# x-BIMU_Bluetooth.net
KiCad netlist of a schematic drawn in EAGLE
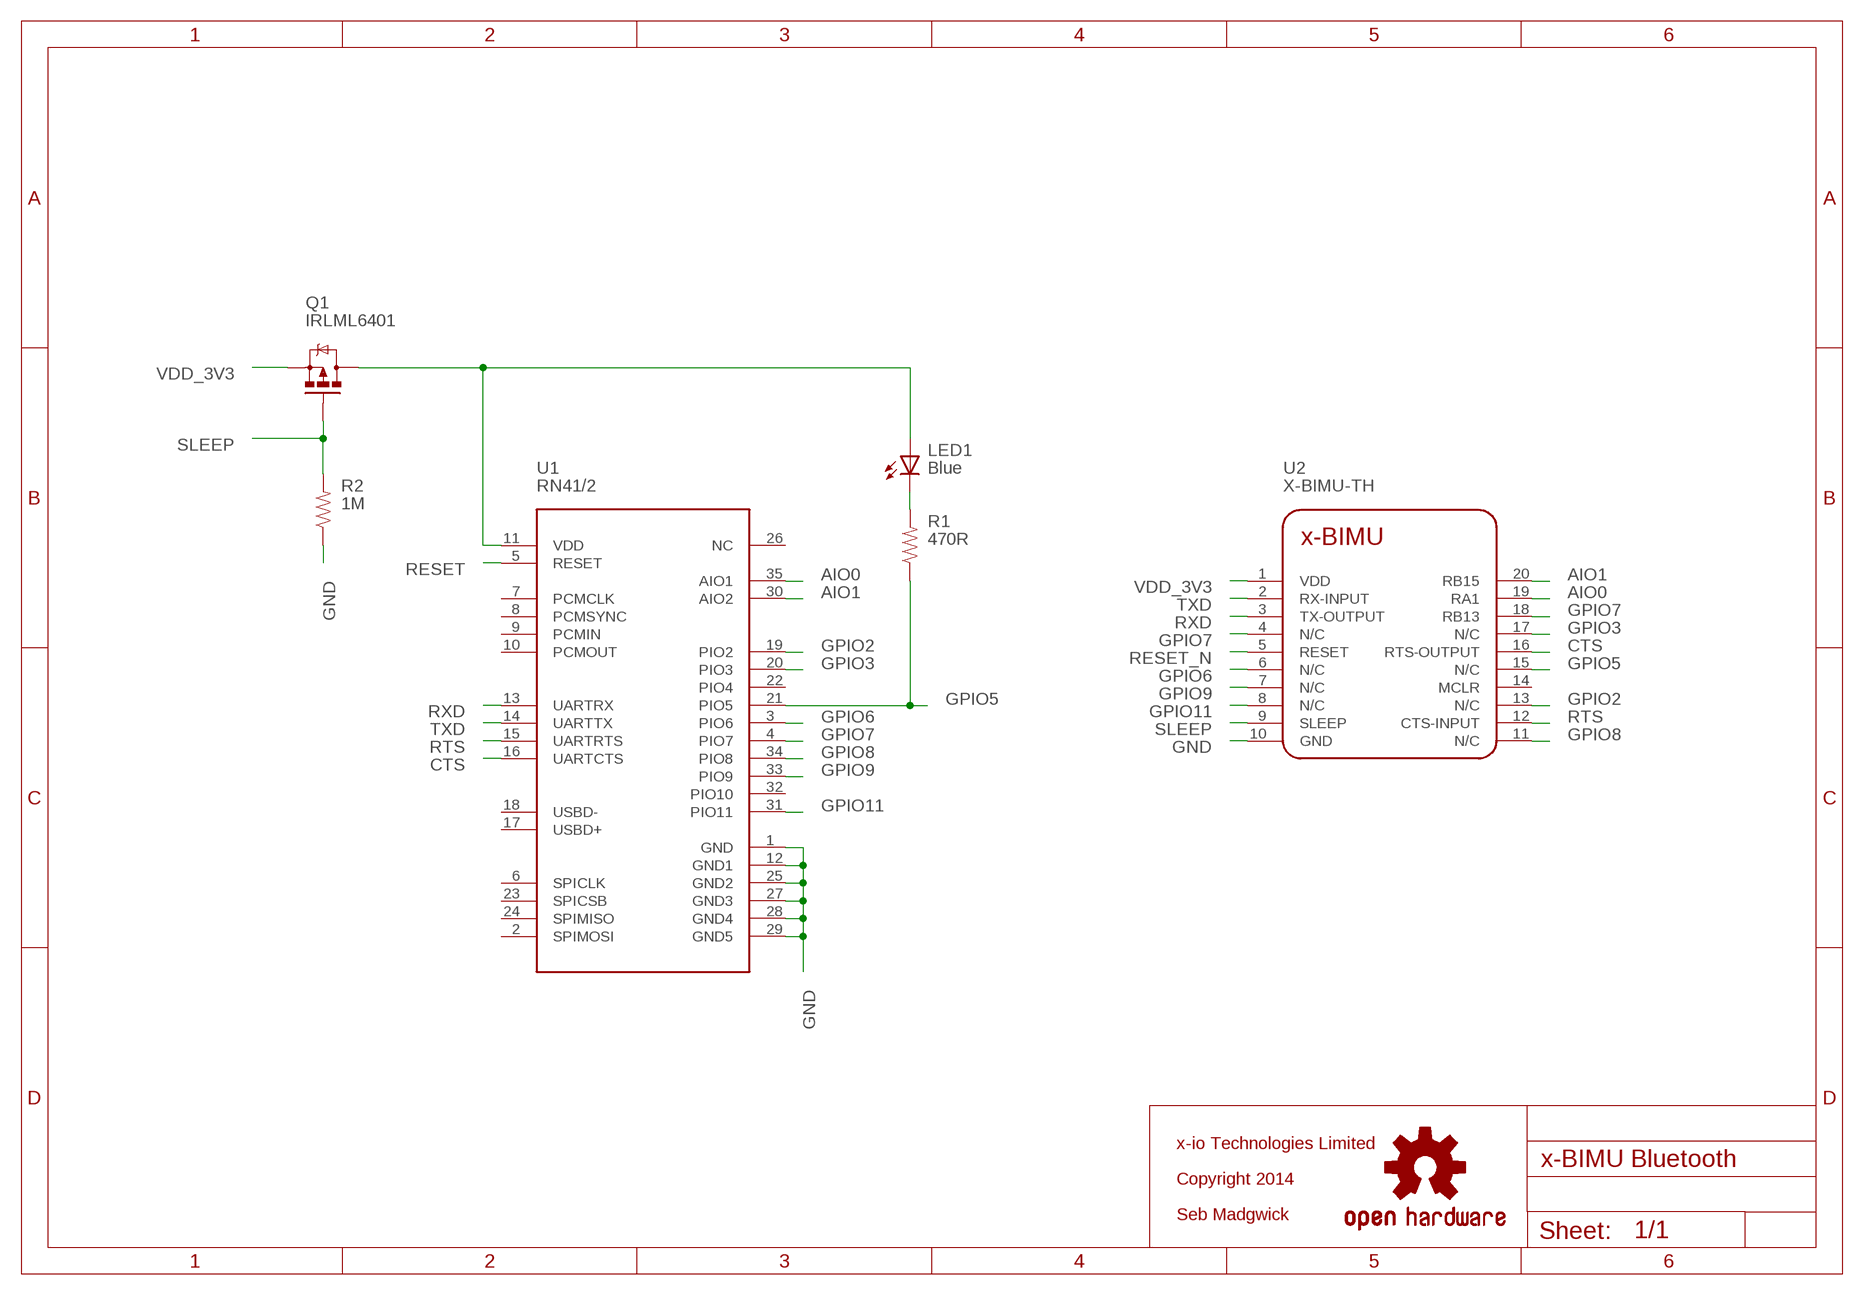
[diagram p0: schematic, sheet 1]

(export (version "E")
  (design (tool "Eeschema 10.0.6"))
  (components
    (comp (ref "LED1")
      (value "Blue")
      (footprint "eagle-import:LED-0603")
      (libsource (lib "eagle-import") (part "LED0603"))
    )
    (comp (ref "Q1")
      (value "IRLML6401")
      (footprint "eagle-import:SOT23")
      (libsource (lib "eagle-import") (part "MOSFET-PCHANNEL"))
    )
    (comp (ref "R1")
      (value "470R")
      (footprint "eagle-import:0402-RES")
      (libsource (lib "eagle-import") (part "RESISTOR0402-RES"))
    )
    (comp (ref "R2")
      (value "1M")
      (footprint "eagle-import:0402-RES")
      (libsource (lib "eagle-import") (part "RESISTOR0402-RES"))
    )
    (comp (ref "U$3")
      (value "OSHW-LOGOS")
      (footprint "eagle-import:OSHW-LOGO-S")
      (libsource (lib "eagle-import") (part "OSHW-LOGOS"))
    )
    (comp (ref "U1")
      (value "RN41/2")
      (footprint "eagle-import:RN41")
      (libsource (lib "eagle-import") (part "BLUETOOTH-RN41{dblquote}"))
    )
    (comp (ref "U2")
      (value "X-BIMU-TH")
      (footprint "eagle-import:X-BIMU_TH")
      (libsource (lib "eagle-import") (part "X-BIMU-TH"))
    )
  )
  (nets
    (net (code "1") (name "/AIO0") (class "Default")
      (node (ref "U1") (pin "35") (pinfunction "AIO1_35") (pintype "bidirectional"))
      (node (ref "U2") (pin "19") (pinfunction "RA1_19") (pintype "bidirectional"))
    )
    (net (code "2") (name "/AIO1") (class "Default")
      (node (ref "U1") (pin "30") (pinfunction "AIO2_30") (pintype "bidirectional"))
      (node (ref "U2") (pin "20") (pinfunction "RB15_20") (pintype "bidirectional"))
    )
    (net (code "3") (name "/CTS") (class "Default")
      (node (ref "U1") (pin "16") (pinfunction "UARTCTS_16") (pintype "bidirectional"))
      (node (ref "U2") (pin "16") (pinfunction "RTS-OUTPUT_16") (pintype "bidirectional"))
    )
    (net (code "4") (name "/GND") (class "Default")
      (node (ref "R2") (pin "1") (pinfunction "1_1") (pintype "passive"))
      (node (ref "U1") (pin "1") (pinfunction "GND_1") (pintype "bidirectional"))
      (node (ref "U1") (pin "12") (pinfunction "GND1_12") (pintype "bidirectional"))
      (node (ref "U1") (pin "25") (pinfunction "GND2_25") (pintype "bidirectional"))
      (node (ref "U1") (pin "27") (pinfunction "GND3_27") (pintype "bidirectional"))
      (node (ref "U1") (pin "28") (pinfunction "GND4_28") (pintype "bidirectional"))
      (node (ref "U1") (pin "29") (pinfunction "GND5_29") (pintype "bidirectional"))
      (node (ref "U2") (pin "10") (pinfunction "GND_10") (pintype "bidirectional"))
    )
    (net (code "5") (name "/GPIO2") (class "Default")
      (node (ref "U1") (pin "19") (pinfunction "PIO2_19") (pintype "bidirectional"))
      (node (ref "U2") (pin "13") (pinfunction "N/C_13") (pintype "bidirectional"))
    )
    (net (code "6") (name "/GPIO3") (class "Default")
      (node (ref "U1") (pin "20") (pinfunction "PIO3_20") (pintype "bidirectional"))
      (node (ref "U2") (pin "17") (pinfunction "N/C_17") (pintype "bidirectional"))
    )
    (net (code "7") (name "/GPIO5") (class "Default")
      (node (ref "R1") (pin "1") (pinfunction "1_1") (pintype "passive"))
      (node (ref "U1") (pin "21") (pinfunction "PIO5_21") (pintype "bidirectional"))
      (node (ref "U2") (pin "15") (pinfunction "N/C_15") (pintype "bidirectional"))
    )
    (net (code "8") (name "/GPIO6") (class "Default")
      (node (ref "U1") (pin "3") (pinfunction "PIO6_3") (pintype "bidirectional"))
      (node (ref "U2") (pin "6") (pinfunction "N/C_6") (pintype "bidirectional"))
    )
    (net (code "9") (name "/GPIO7") (class "Default")
      (node (ref "U1") (pin "4") (pinfunction "PIO7_4") (pintype "bidirectional"))
      (node (ref "U2") (pin "18") (pinfunction "RB13_18") (pintype "bidirectional"))
      (node (ref "U2") (pin "4") (pinfunction "N/C_4") (pintype "bidirectional"))
    )
    (net (code "10") (name "/GPIO8") (class "Default")
      (node (ref "U1") (pin "34") (pinfunction "PIO8_34") (pintype "bidirectional"))
      (node (ref "U2") (pin "11") (pinfunction "N/C_11") (pintype "bidirectional"))
    )
    (net (code "11") (name "/GPIO9") (class "Default")
      (node (ref "U1") (pin "33") (pinfunction "PIO9_33") (pintype "bidirectional"))
      (node (ref "U2") (pin "7") (pinfunction "N/C_7") (pintype "bidirectional"))
    )
    (net (code "12") (name "/GPIO11") (class "Default")
      (node (ref "U1") (pin "31") (pinfunction "PIO11_31") (pintype "bidirectional"))
      (node (ref "U2") (pin "8") (pinfunction "N/C_8") (pintype "bidirectional"))
    )
    (net (code "13") (name "/RESET") (class "Default")
      (node (ref "U1") (pin "5") (pinfunction "RESET_5") (pintype "bidirectional"))
    )
    (net (code "14") (name "/RESET_N") (class "Default")
      (node (ref "U2") (pin "5") (pinfunction "RESET_5") (pintype "bidirectional"))
    )
    (net (code "15") (name "/RTS") (class "Default")
      (node (ref "U1") (pin "15") (pinfunction "UARTRTS_15") (pintype "bidirectional"))
      (node (ref "U2") (pin "12") (pinfunction "CTS-INPUT_12") (pintype "bidirectional"))
    )
    (net (code "16") (name "/RXD") (class "Default")
      (node (ref "U1") (pin "13") (pinfunction "UARTRX_13") (pintype "bidirectional"))
      (node (ref "U2") (pin "3") (pinfunction "TX-OUTPUT_3") (pintype "bidirectional"))
    )
    (net (code "17") (name "/SLEEP") (class "Default")
      (node (ref "Q1") (pin "1") (pinfunction "G_1") (pintype "passive"))
      (node (ref "R2") (pin "2") (pinfunction "2_2") (pintype "passive"))
      (node (ref "U2") (pin "9") (pinfunction "SLEEP_9") (pintype "bidirectional"))
    )
    (net (code "18") (name "/TXD") (class "Default")
      (node (ref "U1") (pin "14") (pinfunction "UARTTX_14") (pintype "bidirectional"))
      (node (ref "U2") (pin "2") (pinfunction "RX-INPUT_2") (pintype "bidirectional"))
    )
    (net (code "19") (name "/VDD_3V3") (class "Default")
      (node (ref "Q1") (pin "2") (pinfunction "S_2") (pintype "passive"))
      (node (ref "U2") (pin "1") (pinfunction "VDD_1") (pintype "bidirectional"))
    )
    (net (code "20") (name "Net-(LED1-PadC)") (class "Default")
      (node (ref "LED1") (pin "C") (pinfunction "C_C") (pintype "passive"))
      (node (ref "R1") (pin "2") (pinfunction "2_2") (pintype "passive"))
    )
    (net (code "21") (name "Net-(Q1-D)") (class "Default")
      (node (ref "LED1") (pin "A") (pinfunction "A_A") (pintype "passive"))
      (node (ref "Q1") (pin "3") (pinfunction "D_3") (pintype "passive"))
      (node (ref "U1") (pin "11") (pinfunction "VDD_11") (pintype "bidirectional"))
    )
    (net (code "22") (name "unconnected-(U1-NC-Pad26)") (class "Default")
      (node (ref "U1") (pin "26") (pinfunction "NC_26") (pintype "bidirectional"))
    )
    (net (code "23") (name "unconnected-(U1-PCMCLK-Pad7)") (class "Default")
      (node (ref "U1") (pin "7") (pinfunction "PCMCLK_7") (pintype "bidirectional"))
    )
    (net (code "24") (name "unconnected-(U1-PCMIN-Pad9)") (class "Default")
      (node (ref "U1") (pin "9") (pinfunction "PCMIN_9") (pintype "bidirectional"))
    )
    (net (code "25") (name "unconnected-(U1-PCMOUT-Pad10)") (class "Default")
      (node (ref "U1") (pin "10") (pinfunction "PCMOUT_10") (pintype "bidirectional"))
    )
    (net (code "26") (name "unconnected-(U1-PCMSYNC-Pad8)") (class "Default")
      (node (ref "U1") (pin "8") (pinfunction "PCMSYNC_8") (pintype "bidirectional"))
    )
    (net (code "27") (name "unconnected-(U1-PIO4-Pad22)") (class "Default")
      (node (ref "U1") (pin "22") (pinfunction "PIO4_22") (pintype "bidirectional"))
    )
    (net (code "28") (name "unconnected-(U1-PIO10-Pad32)") (class "Default")
      (node (ref "U1") (pin "32") (pinfunction "PIO10_32") (pintype "bidirectional"))
    )
    (net (code "29") (name "unconnected-(U1-SPICLK-Pad6)") (class "Default")
      (node (ref "U1") (pin "6") (pinfunction "SPICLK_6") (pintype "bidirectional"))
    )
    (net (code "30") (name "unconnected-(U1-SPICSB-Pad23)") (class "Default")
      (node (ref "U1") (pin "23") (pinfunction "SPICSB_23") (pintype "bidirectional"))
    )
    (net (code "31") (name "unconnected-(U1-SPIMISO-Pad24)") (class "Default")
      (node (ref "U1") (pin "24") (pinfunction "SPIMISO_24") (pintype "bidirectional"))
    )
    (net (code "32") (name "unconnected-(U1-SPIMOSI-Pad2)") (class "Default")
      (node (ref "U1") (pin "2") (pinfunction "SPIMOSI_2") (pintype "bidirectional"))
    )
    (net (code "33") (name "unconnected-(U1-USBD+-Pad17)") (class "Default")
      (node (ref "U1") (pin "17") (pinfunction "USBD+_17") (pintype "bidirectional"))
    )
    (net (code "34") (name "unconnected-(U1-USBD--Pad18)") (class "Default")
      (node (ref "U1") (pin "18") (pinfunction "USBD-_18") (pintype "bidirectional"))
    )
    (net (code "35") (name "unconnected-(U2-MCLR-Pad14)") (class "Default")
      (node (ref "U2") (pin "14") (pinfunction "MCLR_14") (pintype "bidirectional"))
    )
  )
)
